# debug.net
KiCad netlist of a schematic drawn in Altium Designer
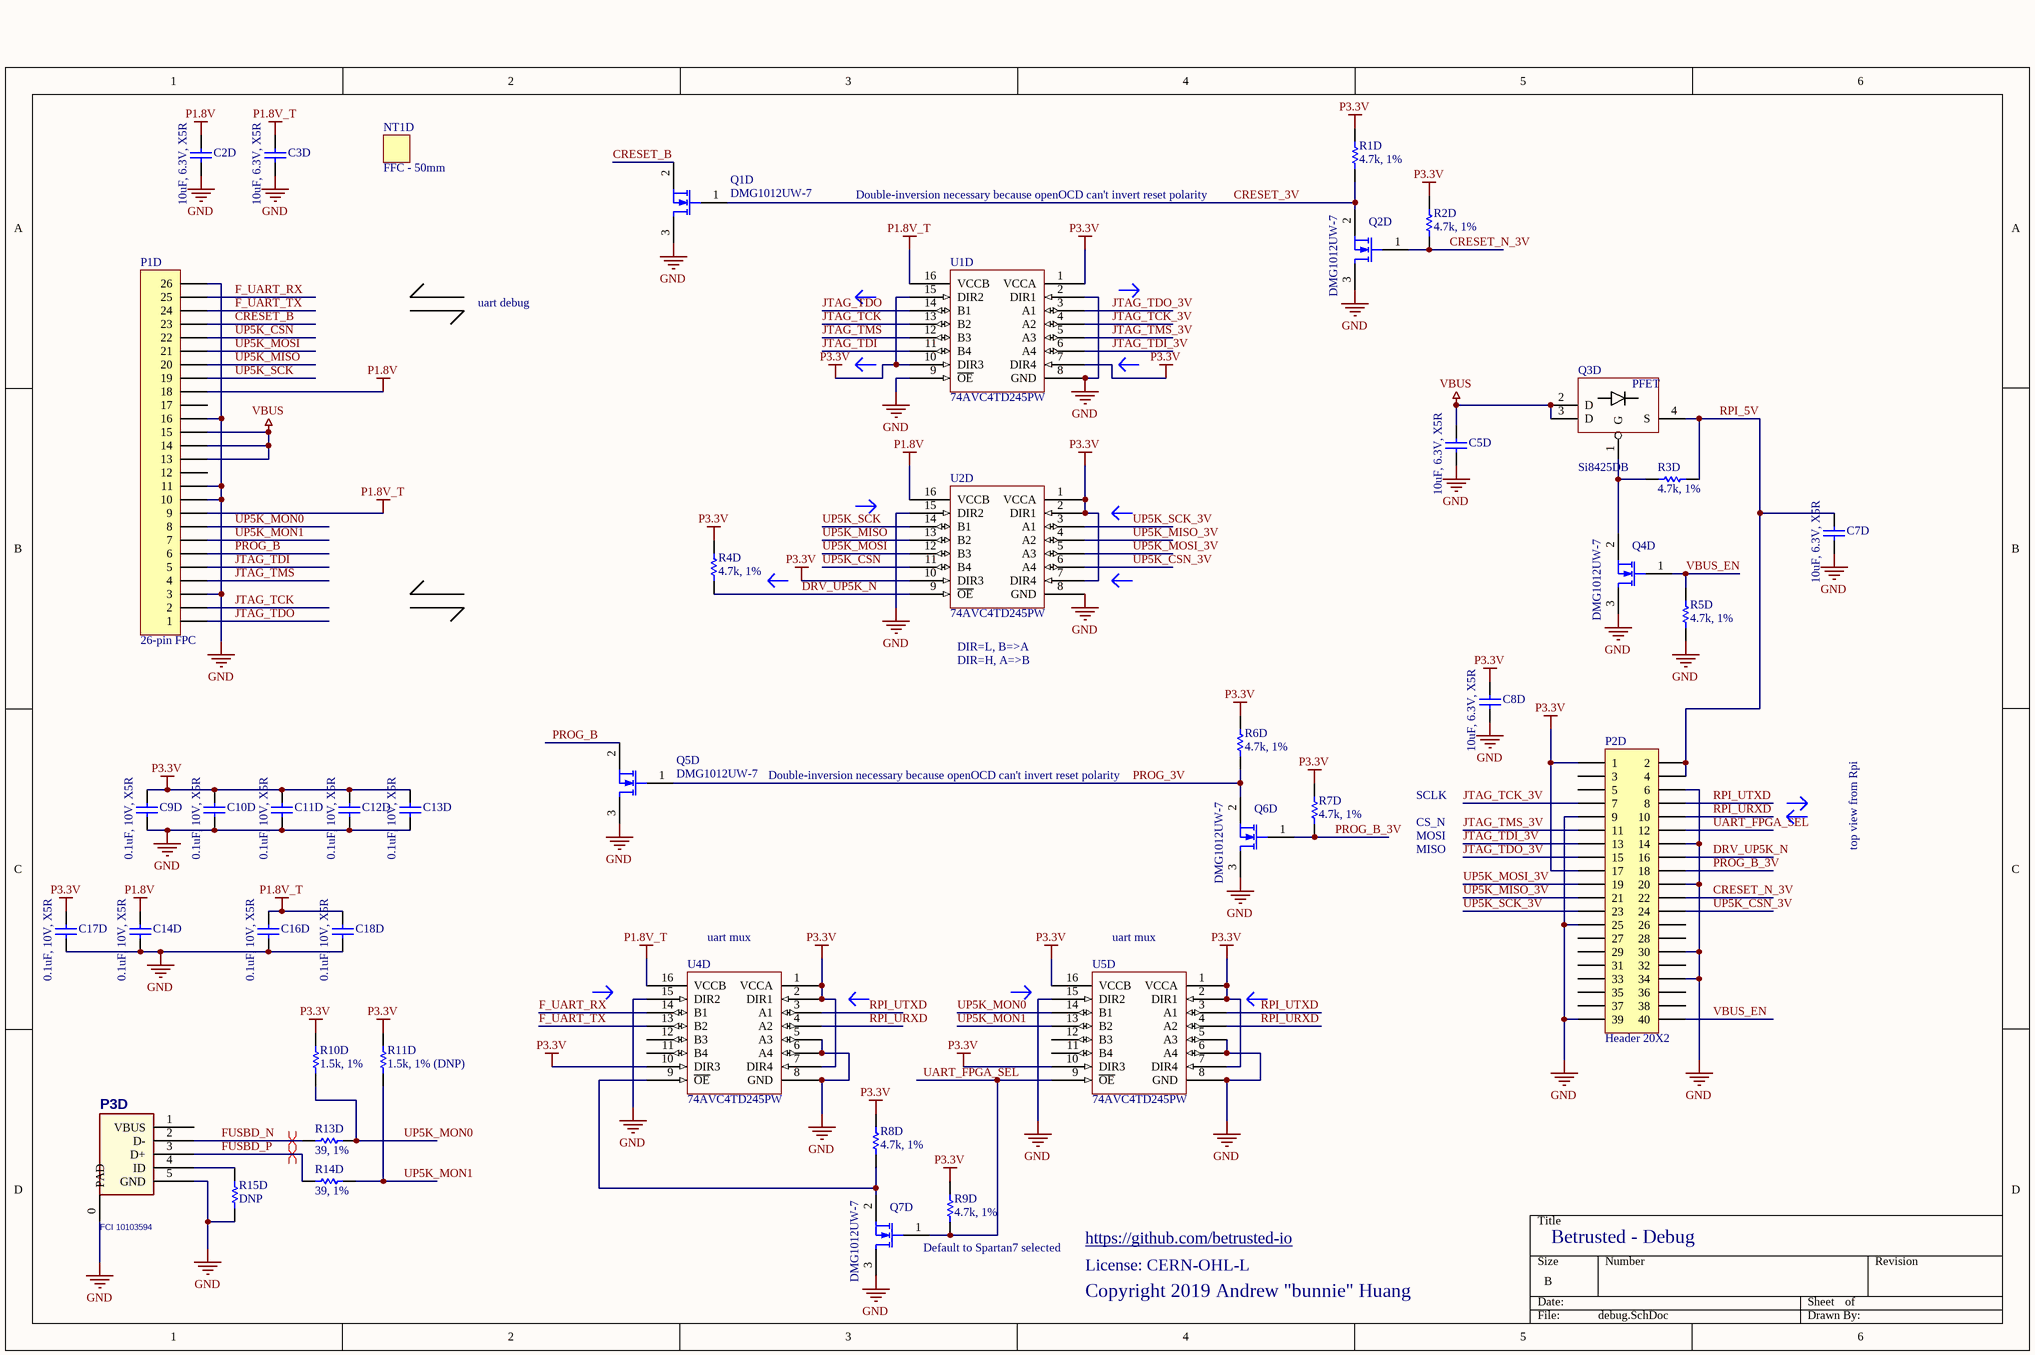
[diagram p0: debug.SchDoc]

(export (version "E")
  (design (tool "Eeschema 10.0.6"))
  (components
    (comp (ref "C2D")
      (value "10uF, 6.3V, X5R")
      (footprint "B_CAP0603")
      (description "Capacitor (Semiconductor SIM Model)")
      (fields (field (name "MPN") "CL10A106MQ8NNNC"))
      (libsource (lib "Miscellaneous Devices") (part "Cap Semi"))
    )
    (comp (ref "C3D")
      (value "10uF, 6.3V, X5R")
      (footprint "B_CAP0603")
      (description "Capacitor (Semiconductor SIM Model)")
      (fields (field (name "MPN") "CL10A106MQ8NNNC"))
      (libsource (lib "Miscellaneous Devices") (part "Cap Semi"))
    )
    (comp (ref "C5D")
      (value "10uF, 6.3V, X5R")
      (footprint "B_CAP0603")
      (description "Capacitor (Semiconductor SIM Model)")
      (fields (field (name "MPN") "CL10A106MQ8NNNC"))
      (libsource (lib "Miscellaneous Devices") (part "Cap Semi"))
    )
    (comp (ref "C7D")
      (value "10uF, 6.3V, X5R")
      (footprint "B_CAP0603")
      (description "Capacitor (Semiconductor SIM Model)")
      (fields (field (name "MPN") "CL10A106MQ8NNNC"))
      (libsource (lib "Miscellaneous Devices") (part "Cap Semi"))
    )
    (comp (ref "C8D")
      (value "10uF, 6.3V, X5R")
      (footprint "B_CAP0603")
      (description "Capacitor (Semiconductor SIM Model)")
      (fields (field (name "MPN") "CL10A106MQ8NNNC"))
      (libsource (lib "Miscellaneous Devices") (part "Cap Semi"))
    )
    (comp (ref "C9D")
      (value "0.1uF, 10V, X5R")
      (footprint "B_CAP0402")
      (description "Capacitor (Semiconductor SIM Model)")
      (fields (field (name "MPN") "CL05A104KP5NNNC"))
      (libsource (lib "Miscellaneous Devices") (part "Cap Semi"))
    )
    (comp (ref "C10D")
      (value "0.1uF, 10V, X5R")
      (footprint "B_CAP0402")
      (description "Capacitor (Semiconductor SIM Model)")
      (fields (field (name "MPN") "CL05A104KP5NNNC"))
      (libsource (lib "Miscellaneous Devices") (part "Cap Semi"))
    )
    (comp (ref "C11D")
      (value "0.1uF, 10V, X5R")
      (footprint "B_CAP0402")
      (description "Capacitor (Semiconductor SIM Model)")
      (fields (field (name "MPN") "CL05A104KP5NNNC"))
      (libsource (lib "Miscellaneous Devices") (part "Cap Semi"))
    )
    (comp (ref "C12D")
      (value "0.1uF, 10V, X5R")
      (footprint "B_CAP0402")
      (description "Capacitor (Semiconductor SIM Model)")
      (fields (field (name "MPN") "CL05A104KP5NNNC"))
      (libsource (lib "Miscellaneous Devices") (part "Cap Semi"))
    )
    (comp (ref "C13D")
      (value "0.1uF, 10V, X5R")
      (footprint "B_CAP0402")
      (description "Capacitor (Semiconductor SIM Model)")
      (fields (field (name "MPN") "CL05A104KP5NNNC"))
      (libsource (lib "Miscellaneous Devices") (part "Cap Semi"))
    )
    (comp (ref "C14D")
      (value "0.1uF, 10V, X5R")
      (footprint "B_CAP0402")
      (description "Capacitor (Semiconductor SIM Model)")
      (fields (field (name "MPN") "CL05A104KP5NNNC"))
      (libsource (lib "Miscellaneous Devices") (part "Cap Semi"))
    )
    (comp (ref "C16D")
      (value "0.1uF, 10V, X5R")
      (footprint "B_CAP0402")
      (description "Capacitor (Semiconductor SIM Model)")
      (fields (field (name "MPN") "CL05A104KP5NNNC"))
      (libsource (lib "Miscellaneous Devices") (part "Cap Semi"))
    )
    (comp (ref "C17D")
      (value "0.1uF, 10V, X5R")
      (footprint "B_CAP0402")
      (description "Capacitor (Semiconductor SIM Model)")
      (fields (field (name "MPN") "CL05A104KP5NNNC"))
      (libsource (lib "Miscellaneous Devices") (part "Cap Semi"))
    )
    (comp (ref "C18D")
      (value "0.1uF, 10V, X5R")
      (footprint "B_CAP0402")
      (description "Capacitor (Semiconductor SIM Model)")
      (fields (field (name "MPN") "CL05A104KP5NNNC"))
      (libsource (lib "Miscellaneous Devices") (part "Cap Semi"))
    )
    (comp (ref "NT1D")
      (value "FFC - 50mm")
      (description "Placeholder for non-board BOM items")
      (fields (field (name "MPN") "FJH-26-D-02.00-4"))
      (libsource (lib "commonsch") (part "NOTE"))
    )
    (comp (ref "P1D")
      (value "26-pin FPC")
      (footprint "HRS_FH34SRJ-26S-0.5SH(50)")
      (description "26 Pin FPC header")
      (fields (field (name "MPN") "FH34SRJ-26S-0.5SH(99)"))
      (libsource (lib "commonsch-new") (part "FPC-26"))
    )
    (comp (ref "P2D")
      (value "Header 20X2")
      (footprint "SAMTEC_SSW-120-01-F-D")
      (description "Header, 20-Pin, Dual row")
      (fields (field (name "PUBLISHER") "Altium Limited"))
      (libsource (lib "Miscellaneous Connectors") (part "Header 20X2"))
    )
    (comp (ref "P3D")
      (value "FCI 10103594")
      (footprint "USB_MICRO_B_SMT")
      (description "Micro USB B type connector")
      (fields (field (name "MPN") "10103594-0001LF"))
      (libsource (lib "*") (part "USB_MINI-AB_1"))
    )
    (comp (ref "Q1D")
      (value "DMG1012UW-7")
      (footprint "SOT323-3AN")
      (description "N-Channel MOSFET")
      (fields (field (name "PUBLISHER") "Altium Limited"))
      (libsource (lib "Miscellaneous Devices") (part "MOSFET-N"))
    )
    (comp (ref "Q2D")
      (value "DMG1012UW-7")
      (footprint "SOT323-3AN")
      (description "N-Channel MOSFET")
      (fields (field (name "PUBLISHER") "Altium Limited"))
      (libsource (lib "Miscellaneous Devices") (part "MOSFET-N"))
    )
    (comp (ref "Q3D")
      (value "Si8425DB")
      (footprint "VISHAY_MICRO_FOOT_4_BUMP")
      (description "P-channel 20V 6.2A 27mOhm @ -2.5V")
      (fields (field (name "MPN") "SI8457DB-T1-E1"))
      (libsource (lib "temp-to-merge") (part "Si8425DB"))
    )
    (comp (ref "Q4D")
      (value "DMG1012UW-7")
      (footprint "SOT323-3AN")
      (description "N-Channel MOSFET")
      (fields (field (name "PUBLISHER") "Altium Limited"))
      (libsource (lib "Miscellaneous Devices") (part "MOSFET-N"))
    )
    (comp (ref "Q5D")
      (value "DMG1012UW-7")
      (footprint "SOT323-3AN")
      (description "N-Channel MOSFET")
      (fields (field (name "PUBLISHER") "Altium Limited"))
      (libsource (lib "Miscellaneous Devices") (part "MOSFET-N"))
    )
    (comp (ref "Q6D")
      (value "DMG1012UW-7")
      (footprint "SOT323-3AN")
      (description "N-Channel MOSFET")
      (fields (field (name "PUBLISHER") "Altium Limited"))
      (libsource (lib "Miscellaneous Devices") (part "MOSFET-N"))
    )
    (comp (ref "Q7D")
      (value "DMG1012UW-7")
      (footprint "SOT323-3AN")
      (description "N-Channel MOSFET")
      (fields (field (name "PUBLISHER") "Altium Limited"))
      (libsource (lib "Miscellaneous Devices") (part "MOSFET-N"))
    )
    (comp (ref "R1D")
      (value "4.7k, 1%")
      (footprint "B_RES0402")
      (description "Resistor")
      (fields (field (name "MPN") "ANY"))
      (libsource (lib "Miscellaneous Devices") (part "Res1"))
    )
    (comp (ref "R2D")
      (value "4.7k, 1%")
      (footprint "B_RES0402")
      (description "Resistor")
      (fields (field (name "MPN") "ANY"))
      (libsource (lib "Miscellaneous Devices") (part "Res1"))
    )
    (comp (ref "R3D")
      (value "4.7k, 1%")
      (footprint "B_RES0402")
      (description "Resistor")
      (fields (field (name "MPN") "ANY"))
      (libsource (lib "Miscellaneous Devices") (part "Res1"))
    )
    (comp (ref "R4D")
      (value "4.7k, 1%")
      (footprint "B_RES0402")
      (description "Resistor")
      (fields (field (name "MPN") "ANY"))
      (libsource (lib "Miscellaneous Devices") (part "Res1"))
    )
    (comp (ref "R5D")
      (value "4.7k, 1%")
      (footprint "B_RES0402")
      (description "Resistor")
      (fields (field (name "MPN") "ANY"))
      (libsource (lib "Miscellaneous Devices") (part "Res1"))
    )
    (comp (ref "R6D")
      (value "4.7k, 1%")
      (footprint "B_RES0402")
      (description "Resistor")
      (fields (field (name "MPN") "ANY"))
      (libsource (lib "Miscellaneous Devices") (part "Res1"))
    )
    (comp (ref "R7D")
      (value "4.7k, 1%")
      (footprint "B_RES0402")
      (description "Resistor")
      (fields (field (name "MPN") "ANY"))
      (libsource (lib "Miscellaneous Devices") (part "Res1"))
    )
    (comp (ref "R8D")
      (value "4.7k, 1%")
      (footprint "B_RES0402")
      (description "Resistor")
      (fields (field (name "MPN") "ANY"))
      (libsource (lib "Miscellaneous Devices") (part "Res1"))
    )
    (comp (ref "R9D")
      (value "4.7k, 1%")
      (footprint "B_RES0402")
      (description "Resistor")
      (fields (field (name "MPN") "ANY"))
      (libsource (lib "Miscellaneous Devices") (part "Res1"))
    )
    (comp (ref "R10D")
      (value "1.5k, 1%")
      (footprint "B_RES0402")
      (description "Resistor")
      (fields (field (name "MPN") "RS02U152FT"))
      (libsource (lib "Miscellaneous Devices") (part "Res1"))
    )
    (comp (ref "R11D")
      (value "1.5k, 1% (DNP)")
      (footprint "B_RES0402")
      (description "Resistor")
      (fields (field (name "MPN") "DNP"))
      (libsource (lib "Miscellaneous Devices") (part "Res1"))
    )
    (comp (ref "R13D")
      (value "39, 1%")
      (footprint "B_RES0402")
      (description "Resistor")
      (fields (field (name "MPN") "ANY"))
      (libsource (lib "Miscellaneous Devices") (part "Res1"))
    )
    (comp (ref "R14D")
      (value "39, 1%")
      (footprint "B_RES0402")
      (description "Resistor")
      (fields (field (name "MPN") "ANY"))
      (libsource (lib "Miscellaneous Devices") (part "Res1"))
    )
    (comp (ref "R15D")
      (value "DNP")
      (footprint "B_RES0402")
      (description "Resistor")
      (fields (field (name "MPN") "ANY"))
      (libsource (lib "Miscellaneous Devices") (part "Res1"))
    )
    (comp (ref "U1D")
      (value "74AVC4TD245PW")
      (footprint "TSOP65P640-16AN")
      (description "4-bit dual supply translating transceiver with configurable voltage translation; 3-state")
      (libsource (lib "commonsch-new") (part "74AVC4TD245"))
    )
    (comp (ref "U2D")
      (value "74AVC4TD245PW")
      (footprint "TSOP65P640-16AN")
      (description "4-bit dual supply translating transceiver with configurable voltage translation; 3-state")
      (libsource (lib "commonsch-new") (part "74AVC4TD245"))
    )
    (comp (ref "U4D")
      (value "74AVC4TD245PW")
      (footprint "TSOP65P640-16AN")
      (description "4-bit dual supply translating transceiver with configurable voltage translation; 3-state")
      (libsource (lib "commonsch-new") (part "74AVC4TD245"))
    )
    (comp (ref "U5D")
      (value "74AVC4TD245PW")
      (footprint "TSOP65P640-16AN")
      (description "4-bit dual supply translating transceiver with configurable voltage translation; 3-state")
      (libsource (lib "commonsch-new") (part "74AVC4TD245"))
    )
  )
  (nets
    (net (code "1") (name "/CRESET_3V") (class "Default")
      (node (ref "Q1D") (pin "1") (pinfunction "G_1") (pintype "passive"))
      (node (ref "Q2D") (pin "2") (pinfunction "S_2") (pintype "passive"))
      (node (ref "R1D") (pin "1") (pinfunction "1_1") (pintype "passive"))
    )
    (net (code "2") (name "/CRESET_B") (class "Default")
      (node (ref "P1D") (pin "23") (pinfunction "23_23") (pintype "passive"))
      (node (ref "Q1D") (pin "2") (pinfunction "S_2") (pintype "passive"))
    )
    (net (code "3") (name "/CRESET_N_3V") (class "Default")
      (node (ref "P2D") (pin "22") (pinfunction "22_22") (pintype "passive"))
      (node (ref "Q2D") (pin "1") (pinfunction "G_1") (pintype "passive"))
      (node (ref "R2D") (pin "1") (pinfunction "1_1") (pintype "passive"))
    )
    (net (code "4") (name "/DRV_UP5K_N") (class "Default")
      (node (ref "P2D") (pin "16") (pinfunction "16_16") (pintype "passive"))
      (node (ref "R4D") (pin "1") (pinfunction "1_1") (pintype "passive"))
      (node (ref "U2D") (pin "9") (pinfunction "~{OE}_9") (pintype "input"))
    )
    (net (code "5") (name "/FUSBD_N") (class "Default")
      (node (ref "P3D") (pin "2") (pinfunction "D-_2") (pintype "passive"))
      (node (ref "R13D") (pin "2") (pinfunction "2_2") (pintype "passive"))
    )
    (net (code "6") (name "/FUSBD_P") (class "Default")
      (node (ref "P3D") (pin "3") (pinfunction "D+_3") (pintype "passive"))
      (node (ref "R14D") (pin "2") (pinfunction "2_2") (pintype "passive"))
    )
    (net (code "7") (name "/F_UART_RX") (class "Default")
      (node (ref "P1D") (pin "25") (pinfunction "25_25") (pintype "passive"))
      (node (ref "U4D") (pin "14") (pinfunction "B1_14") (pintype "bidirectional"))
    )
    (net (code "8") (name "/F_UART_TX") (class "Default")
      (node (ref "P1D") (pin "24") (pinfunction "24_24") (pintype "passive"))
      (node (ref "U4D") (pin "13") (pinfunction "B2_13") (pintype "bidirectional"))
    )
    (net (code "9") (name "/JTAG_TCK") (class "Default")
      (node (ref "P1D") (pin "2") (pinfunction "2_2") (pintype "passive"))
      (node (ref "U1D") (pin "13") (pinfunction "B2_13") (pintype "bidirectional"))
    )
    (net (code "10") (name "/JTAG_TCK_3V") (class "Default")
      (node (ref "P2D") (pin "7") (pinfunction "7_7") (pintype "passive"))
      (node (ref "U1D") (pin "4") (pinfunction "A2_4") (pintype "bidirectional"))
    )
    (net (code "11") (name "/JTAG_TDI") (class "Default")
      (node (ref "P1D") (pin "5") (pinfunction "5_5") (pintype "passive"))
      (node (ref "U1D") (pin "11") (pinfunction "B4_11") (pintype "bidirectional"))
    )
    (net (code "12") (name "/JTAG_TDI_3V") (class "Default")
      (node (ref "P2D") (pin "13") (pinfunction "13_13") (pintype "passive"))
      (node (ref "U1D") (pin "6") (pinfunction "A4_6") (pintype "bidirectional"))
    )
    (net (code "13") (name "/JTAG_TDO") (class "Default")
      (node (ref "P1D") (pin "1") (pinfunction "1_1") (pintype "passive"))
      (node (ref "U1D") (pin "14") (pinfunction "B1_14") (pintype "bidirectional"))
    )
    (net (code "14") (name "/JTAG_TDO_3V") (class "Default")
      (node (ref "P2D") (pin "15") (pinfunction "15_15") (pintype "passive"))
      (node (ref "U1D") (pin "3") (pinfunction "A1_3") (pintype "bidirectional"))
    )
    (net (code "15") (name "/JTAG_TMS") (class "Default")
      (node (ref "P1D") (pin "4") (pinfunction "4_4") (pintype "passive"))
      (node (ref "U1D") (pin "12") (pinfunction "B3_12") (pintype "bidirectional"))
    )
    (net (code "16") (name "/JTAG_TMS_3V") (class "Default")
      (node (ref "P2D") (pin "11") (pinfunction "11_11") (pintype "passive"))
      (node (ref "U1D") (pin "5") (pinfunction "A3_5") (pintype "bidirectional"))
    )
    (net (code "17") (name "/PROG_3V") (class "Default")
      (node (ref "Q5D") (pin "1") (pinfunction "G_1") (pintype "passive"))
      (node (ref "Q6D") (pin "2") (pinfunction "S_2") (pintype "passive"))
      (node (ref "R6D") (pin "1") (pinfunction "1_1") (pintype "passive"))
    )
    (net (code "18") (name "/PROG_B") (class "Default")
      (node (ref "P1D") (pin "6") (pinfunction "6_6") (pintype "passive"))
      (node (ref "Q5D") (pin "2") (pinfunction "S_2") (pintype "passive"))
    )
    (net (code "19") (name "/PROG_B_3V") (class "Default")
      (node (ref "P2D") (pin "18") (pinfunction "18_18") (pintype "passive"))
      (node (ref "Q6D") (pin "1") (pinfunction "G_1") (pintype "passive"))
      (node (ref "R7D") (pin "1") (pinfunction "1_1") (pintype "passive"))
    )
    (net (code "20") (name "/RPI_5V") (class "Default")
      (node (ref "C7D") (pin "1") (pinfunction "1_1") (pintype "passive"))
      (node (ref "P2D") (pin "2") (pinfunction "2_2") (pintype "passive"))
      (node (ref "P2D") (pin "4") (pinfunction "4_4") (pintype "passive"))
      (node (ref "Q3D") (pin "4") (pinfunction "S_4") (pintype "passive"))
      (node (ref "R3D") (pin "1") (pinfunction "1_1") (pintype "passive"))
    )
    (net (code "21") (name "/RPI_URXD") (class "Default")
      (node (ref "P2D") (pin "10") (pinfunction "10_10") (pintype "passive"))
      (node (ref "U4D") (pin "4") (pinfunction "A2_4") (pintype "bidirectional"))
      (node (ref "U5D") (pin "4") (pinfunction "A2_4") (pintype "bidirectional"))
    )
    (net (code "22") (name "/RPI_UTXD") (class "Default")
      (node (ref "P2D") (pin "8") (pinfunction "8_8") (pintype "passive"))
      (node (ref "U4D") (pin "3") (pinfunction "A1_3") (pintype "bidirectional"))
      (node (ref "U5D") (pin "3") (pinfunction "A1_3") (pintype "bidirectional"))
    )
    (net (code "23") (name "/UART_FPGA_SEL") (class "Default")
      (node (ref "P2D") (pin "12") (pinfunction "12_12") (pintype "passive"))
      (node (ref "Q7D") (pin "1") (pinfunction "G_1") (pintype "passive"))
      (node (ref "R9D") (pin "1") (pinfunction "1_1") (pintype "passive"))
      (node (ref "U5D") (pin "9") (pinfunction "~{OE}_9") (pintype "input"))
    )
    (net (code "24") (name "/UP5K_CSN") (class "Default")
      (node (ref "P1D") (pin "22") (pinfunction "22_22") (pintype "passive"))
      (node (ref "U2D") (pin "11") (pinfunction "B4_11") (pintype "bidirectional"))
    )
    (net (code "25") (name "/UP5K_CSN_3V") (class "Default")
      (node (ref "P2D") (pin "24") (pinfunction "24_24") (pintype "passive"))
      (node (ref "U2D") (pin "6") (pinfunction "A4_6") (pintype "bidirectional"))
    )
    (net (code "26") (name "/UP5K_MISO") (class "Default")
      (node (ref "P1D") (pin "20") (pinfunction "20_20") (pintype "passive"))
      (node (ref "U2D") (pin "13") (pinfunction "B2_13") (pintype "bidirectional"))
    )
    (net (code "27") (name "/UP5K_MISO_3V") (class "Default")
      (node (ref "P2D") (pin "21") (pinfunction "21_21") (pintype "passive"))
      (node (ref "U2D") (pin "4") (pinfunction "A2_4") (pintype "bidirectional"))
    )
    (net (code "28") (name "/UP5K_MON0") (class "Default")
      (node (ref "P1D") (pin "8") (pinfunction "8_8") (pintype "passive"))
      (node (ref "R10D") (pin "2") (pinfunction "2_2") (pintype "passive"))
      (node (ref "R13D") (pin "1") (pinfunction "1_1") (pintype "passive"))
      (node (ref "U5D") (pin "14") (pinfunction "B1_14") (pintype "bidirectional"))
    )
    (net (code "29") (name "/UP5K_MON1") (class "Default")
      (node (ref "P1D") (pin "7") (pinfunction "7_7") (pintype "passive"))
      (node (ref "R11D") (pin "2") (pinfunction "2_2") (pintype "passive"))
      (node (ref "R14D") (pin "1") (pinfunction "1_1") (pintype "passive"))
      (node (ref "U5D") (pin "13") (pinfunction "B2_13") (pintype "bidirectional"))
    )
    (net (code "30") (name "/UP5K_MOSI") (class "Default")
      (node (ref "P1D") (pin "21") (pinfunction "21_21") (pintype "passive"))
      (node (ref "U2D") (pin "12") (pinfunction "B3_12") (pintype "bidirectional"))
    )
    (net (code "31") (name "/UP5K_MOSI_3V") (class "Default")
      (node (ref "P2D") (pin "19") (pinfunction "19_19") (pintype "passive"))
      (node (ref "U2D") (pin "5") (pinfunction "A3_5") (pintype "bidirectional"))
    )
    (net (code "32") (name "/UP5K_SCK") (class "Default")
      (node (ref "P1D") (pin "19") (pinfunction "19_19") (pintype "passive"))
      (node (ref "U2D") (pin "14") (pinfunction "B1_14") (pintype "bidirectional"))
    )
    (net (code "33") (name "/UP5K_SCK_3V") (class "Default")
      (node (ref "P2D") (pin "23") (pinfunction "23_23") (pintype "passive"))
      (node (ref "U2D") (pin "3") (pinfunction "A1_3") (pintype "bidirectional"))
    )
    (net (code "34") (name "/VBUS_EN") (class "Default")
      (node (ref "P2D") (pin "40") (pinfunction "40_40") (pintype "passive"))
      (node (ref "Q4D") (pin "1") (pinfunction "G_1") (pintype "passive"))
      (node (ref "R5D") (pin "2") (pinfunction "2_2") (pintype "passive"))
    )
    (net (code "35") (name "GND") (class "Default")
      (node (ref "C10D") (pin "2") (pinfunction "2_2") (pintype "passive"))
      (node (ref "C11D") (pin "2") (pinfunction "2_2") (pintype "passive"))
      (node (ref "C12D") (pin "2") (pinfunction "2_2") (pintype "passive"))
      (node (ref "C13D") (pin "2") (pinfunction "2_2") (pintype "passive"))
      (node (ref "C14D") (pin "2") (pinfunction "2_2") (pintype "passive"))
      (node (ref "C16D") (pin "2") (pinfunction "2_2") (pintype "passive"))
      (node (ref "C17D") (pin "2") (pinfunction "2_2") (pintype "passive"))
      (node (ref "C18D") (pin "2") (pinfunction "2_2") (pintype "passive"))
      (node (ref "C2D") (pin "2") (pinfunction "2_2") (pintype "passive"))
      (node (ref "C3D") (pin "2") (pinfunction "2_2") (pintype "passive"))
      (node (ref "C5D") (pin "2") (pinfunction "2_2") (pintype "passive"))
      (node (ref "C7D") (pin "2") (pinfunction "2_2") (pintype "passive"))
      (node (ref "C8D") (pin "2") (pinfunction "2_2") (pintype "passive"))
      (node (ref "C9D") (pin "2") (pinfunction "2_2") (pintype "passive"))
      (node (ref "P1D") (pin "10") (pinfunction "10_10") (pintype "passive"))
      (node (ref "P1D") (pin "11") (pinfunction "11_11") (pintype "passive"))
      (node (ref "P1D") (pin "16") (pinfunction "16_16") (pintype "passive"))
      (node (ref "P1D") (pin "26") (pinfunction "26_26") (pintype "passive"))
      (node (ref "P1D") (pin "3") (pinfunction "3_3") (pintype "passive"))
      (node (ref "P2D") (pin "14") (pinfunction "14_14") (pintype "passive"))
      (node (ref "P2D") (pin "20") (pinfunction "20_20") (pintype "passive"))
      (node (ref "P2D") (pin "25") (pinfunction "25_25") (pintype "passive"))
      (node (ref "P2D") (pin "30") (pinfunction "30_30") (pintype "passive"))
      (node (ref "P2D") (pin "34") (pinfunction "34_34") (pintype "passive"))
      (node (ref "P2D") (pin "39") (pinfunction "39_39") (pintype "passive"))
      (node (ref "P2D") (pin "6") (pinfunction "6_6") (pintype "passive"))
      (node (ref "P2D") (pin "9") (pinfunction "9_9") (pintype "passive"))
      (node (ref "P3D") (pin "0") (pinfunction "PAD_0") (pintype "passive"))
      (node (ref "P3D") (pin "5") (pinfunction "GND_5") (pintype "passive"))
      (node (ref "Q1D") (pin "3") (pinfunction "D_3") (pintype "passive"))
      (node (ref "Q2D") (pin "3") (pinfunction "D_3") (pintype "passive"))
      (node (ref "Q4D") (pin "3") (pinfunction "D_3") (pintype "passive"))
      (node (ref "Q5D") (pin "3") (pinfunction "D_3") (pintype "passive"))
      (node (ref "Q6D") (pin "3") (pinfunction "D_3") (pintype "passive"))
      (node (ref "Q7D") (pin "3") (pinfunction "D_3") (pintype "passive"))
      (node (ref "R15D") (pin "2") (pinfunction "2_2") (pintype "passive"))
      (node (ref "R5D") (pin "1") (pinfunction "1_1") (pintype "passive"))
      (node (ref "U1D") (pin "2") (pinfunction "DIR1_2") (pintype "input"))
      (node (ref "U1D") (pin "8") (pinfunction "GND_8") (pintype "power_in"))
      (node (ref "U1D") (pin "9") (pinfunction "~{OE}_9") (pintype "input"))
      (node (ref "U2D") (pin "15") (pinfunction "DIR2_15") (pintype "input"))
      (node (ref "U2D") (pin "8") (pinfunction "GND_8") (pintype "power_in"))
      (node (ref "U4D") (pin "15") (pinfunction "DIR2_15") (pintype "input"))
      (node (ref "U4D") (pin "5") (pinfunction "A3_5") (pintype "bidirectional"))
      (node (ref "U4D") (pin "6") (pinfunction "A4_6") (pintype "bidirectional"))
      (node (ref "U4D") (pin "8") (pinfunction "GND_8") (pintype "power_in"))
      (node (ref "U5D") (pin "15") (pinfunction "DIR2_15") (pintype "input"))
      (node (ref "U5D") (pin "5") (pinfunction "A3_5") (pintype "bidirectional"))
      (node (ref "U5D") (pin "6") (pinfunction "A4_6") (pintype "bidirectional"))
      (node (ref "U5D") (pin "8") (pinfunction "GND_8") (pintype "power_in"))
    )
    (net (code "36") (name "Net-(P3D-ID)") (class "Default")
      (node (ref "P3D") (pin "4") (pinfunction "ID_4") (pintype "passive"))
      (node (ref "R15D") (pin "1") (pinfunction "1_1") (pintype "passive"))
    )
    (net (code "37") (name "Net-(Q3D-G)") (class "Default")
      (node (ref "Q3D") (pin "1") (pinfunction "G_1") (pintype "passive"))
      (node (ref "Q4D") (pin "2") (pinfunction "S_2") (pintype "passive"))
      (node (ref "R3D") (pin "2") (pinfunction "2_2") (pintype "passive"))
    )
    (net (code "38") (name "Net-(Q7D-S)") (class "Default")
      (node (ref "Q7D") (pin "2") (pinfunction "S_2") (pintype "passive"))
      (node (ref "R8D") (pin "1") (pinfunction "1_1") (pintype "passive"))
      (node (ref "U4D") (pin "9") (pinfunction "~{OE}_9") (pintype "input"))
    )
    (net (code "39") (name "P1.8V") (class "Default")
      (node (ref "C14D") (pin "1") (pinfunction "1_1") (pintype "passive"))
      (node (ref "C2D") (pin "1") (pinfunction "1_1") (pintype "passive"))
      (node (ref "P1D") (pin "18") (pinfunction "18_18") (pintype "passive"))
      (node (ref "U2D") (pin "16") (pinfunction "VCCB_16") (pintype "power_in"))
    )
    (net (code "40") (name "P1.8V_T") (class "Default")
      (node (ref "C16D") (pin "1") (pinfunction "1_1") (pintype "passive"))
      (node (ref "C18D") (pin "1") (pinfunction "1_1") (pintype "passive"))
      (node (ref "C3D") (pin "1") (pinfunction "1_1") (pintype "passive"))
      (node (ref "P1D") (pin "9") (pinfunction "9_9") (pintype "passive"))
      (node (ref "U1D") (pin "16") (pinfunction "VCCB_16") (pintype "power_in"))
      (node (ref "U4D") (pin "16") (pinfunction "VCCB_16") (pintype "power_in"))
    )
    (net (code "41") (name "P3.3V") (class "Default")
      (node (ref "C10D") (pin "1") (pinfunction "1_1") (pintype "passive"))
      (node (ref "C11D") (pin "1") (pinfunction "1_1") (pintype "passive"))
      (node (ref "C12D") (pin "1") (pinfunction "1_1") (pintype "passive"))
      (node (ref "C13D") (pin "1") (pinfunction "1_1") (pintype "passive"))
      (node (ref "C17D") (pin "1") (pinfunction "1_1") (pintype "passive"))
      (node (ref "C8D") (pin "1") (pinfunction "1_1") (pintype "passive"))
      (node (ref "C9D") (pin "1") (pinfunction "1_1") (pintype "passive"))
      (node (ref "P2D") (pin "1") (pinfunction "1_1") (pintype "passive"))
      (node (ref "P2D") (pin "17") (pinfunction "17_17") (pintype "passive"))
      (node (ref "R10D") (pin "1") (pinfunction "1_1") (pintype "passive"))
      (node (ref "R11D") (pin "1") (pinfunction "1_1") (pintype "passive"))
      (node (ref "R1D") (pin "2") (pinfunction "2_2") (pintype "passive"))
      (node (ref "R2D") (pin "2") (pinfunction "2_2") (pintype "passive"))
      (node (ref "R4D") (pin "2") (pinfunction "2_2") (pintype "passive"))
      (node (ref "R6D") (pin "2") (pinfunction "2_2") (pintype "passive"))
      (node (ref "R7D") (pin "2") (pinfunction "2_2") (pintype "passive"))
      (node (ref "R8D") (pin "2") (pinfunction "2_2") (pintype "passive"))
      (node (ref "R9D") (pin "2") (pinfunction "2_2") (pintype "passive"))
      (node (ref "U1D") (pin "1") (pinfunction "VCCA_1") (pintype "power_in"))
      (node (ref "U1D") (pin "10") (pinfunction "DIR3_10") (pintype "input"))
      (node (ref "U1D") (pin "15") (pinfunction "DIR2_15") (pintype "input"))
      (node (ref "U1D") (pin "7") (pinfunction "DIR4_7") (pintype "input"))
      (node (ref "U2D") (pin "1") (pinfunction "VCCA_1") (pintype "power_in"))
      (node (ref "U2D") (pin "10") (pinfunction "DIR3_10") (pintype "input"))
      (node (ref "U2D") (pin "2") (pinfunction "DIR1_2") (pintype "input"))
      (node (ref "U2D") (pin "7") (pinfunction "DIR4_7") (pintype "input"))
      (node (ref "U4D") (pin "1") (pinfunction "VCCA_1") (pintype "power_in"))
      (node (ref "U4D") (pin "10") (pinfunction "DIR3_10") (pintype "input"))
      (node (ref "U4D") (pin "2") (pinfunction "DIR1_2") (pintype "input"))
      (node (ref "U4D") (pin "7") (pinfunction "DIR4_7") (pintype "input"))
      (node (ref "U5D") (pin "1") (pinfunction "VCCA_1") (pintype "power_in"))
      (node (ref "U5D") (pin "10") (pinfunction "DIR3_10") (pintype "input"))
      (node (ref "U5D") (pin "16") (pinfunction "VCCB_16") (pintype "power_in"))
      (node (ref "U5D") (pin "2") (pinfunction "DIR1_2") (pintype "input"))
      (node (ref "U5D") (pin "7") (pinfunction "DIR4_7") (pintype "input"))
    )
    (net (code "42") (name "VBUS") (class "Default")
      (node (ref "C5D") (pin "1") (pinfunction "1_1") (pintype "passive"))
      (node (ref "P1D") (pin "13") (pinfunction "13_13") (pintype "passive"))
      (node (ref "P1D") (pin "14") (pinfunction "14_14") (pintype "passive"))
      (node (ref "P1D") (pin "15") (pinfunction "15_15") (pintype "passive"))
      (node (ref "Q3D") (pin "2") (pinfunction "D_2") (pintype "passive"))
      (node (ref "Q3D") (pin "3") (pinfunction "D_3") (pintype "passive"))
    )
    (net (code "43") (name "unconnected-(P1D-Pad12)") (class "Default")
      (node (ref "P1D") (pin "12") (pinfunction "12_12") (pintype "passive"))
    )
    (net (code "44") (name "unconnected-(P1D-Pad17)") (class "Default")
      (node (ref "P1D") (pin "17") (pinfunction "17_17") (pintype "passive"))
    )
    (net (code "45") (name "unconnected-(P2D-Pad3)") (class "Default")
      (node (ref "P2D") (pin "3") (pinfunction "3_3") (pintype "passive"))
    )
    (net (code "46") (name "unconnected-(P2D-Pad5)") (class "Default")
      (node (ref "P2D") (pin "5") (pinfunction "5_5") (pintype "passive"))
    )
    (net (code "47") (name "unconnected-(P2D-Pad26)") (class "Default")
      (node (ref "P2D") (pin "26") (pinfunction "26_26") (pintype "passive"))
    )
    (net (code "48") (name "unconnected-(P2D-Pad27)") (class "Default")
      (node (ref "P2D") (pin "27") (pinfunction "27_27") (pintype "passive"))
    )
    (net (code "49") (name "unconnected-(P2D-Pad28)") (class "Default")
      (node (ref "P2D") (pin "28") (pinfunction "28_28") (pintype "passive"))
    )
    (net (code "50") (name "unconnected-(P2D-Pad29)") (class "Default")
      (node (ref "P2D") (pin "29") (pinfunction "29_29") (pintype "passive"))
    )
    (net (code "51") (name "unconnected-(P2D-Pad31)") (class "Default")
      (node (ref "P2D") (pin "31") (pinfunction "31_31") (pintype "passive"))
    )
    (net (code "52") (name "unconnected-(P2D-Pad32)") (class "Default")
      (node (ref "P2D") (pin "32") (pinfunction "32_32") (pintype "passive"))
    )
    (net (code "53") (name "unconnected-(P2D-Pad33)") (class "Default")
      (node (ref "P2D") (pin "33") (pinfunction "33_33") (pintype "passive"))
    )
    (net (code "54") (name "unconnected-(P2D-Pad35)") (class "Default")
      (node (ref "P2D") (pin "35") (pinfunction "35_35") (pintype "passive"))
    )
    (net (code "55") (name "unconnected-(P2D-Pad36)") (class "Default")
      (node (ref "P2D") (pin "36") (pinfunction "36_36") (pintype "passive"))
    )
    (net (code "56") (name "unconnected-(P2D-Pad37)") (class "Default")
      (node (ref "P2D") (pin "37") (pinfunction "37_37") (pintype "passive"))
    )
    (net (code "57") (name "unconnected-(P2D-Pad38)") (class "Default")
      (node (ref "P2D") (pin "38") (pinfunction "38_38") (pintype "passive"))
    )
    (net (code "58") (name "unconnected-(P3D-VBUS-Pad1)") (class "Default")
      (node (ref "P3D") (pin "1") (pinfunction "VBUS_1") (pintype "passive"))
    )
    (net (code "59") (name "unconnected-(U4D-B3-Pad12)") (class "Default")
      (node (ref "U4D") (pin "12") (pinfunction "B3_12") (pintype "bidirectional"))
    )
    (net (code "60") (name "unconnected-(U4D-B4-Pad11)") (class "Default")
      (node (ref "U4D") (pin "11") (pinfunction "B4_11") (pintype "bidirectional"))
    )
    (net (code "61") (name "unconnected-(U5D-B3-Pad12)") (class "Default")
      (node (ref "U5D") (pin "12") (pinfunction "B3_12") (pintype "bidirectional"))
    )
    (net (code "62") (name "unconnected-(U5D-B4-Pad11)") (class "Default")
      (node (ref "U5D") (pin "11") (pinfunction "B4_11") (pintype "bidirectional"))
    )
  )
)
